# d150_z570m_rev_b.net
KiCad netlist of a schematic drawn in EAGLE
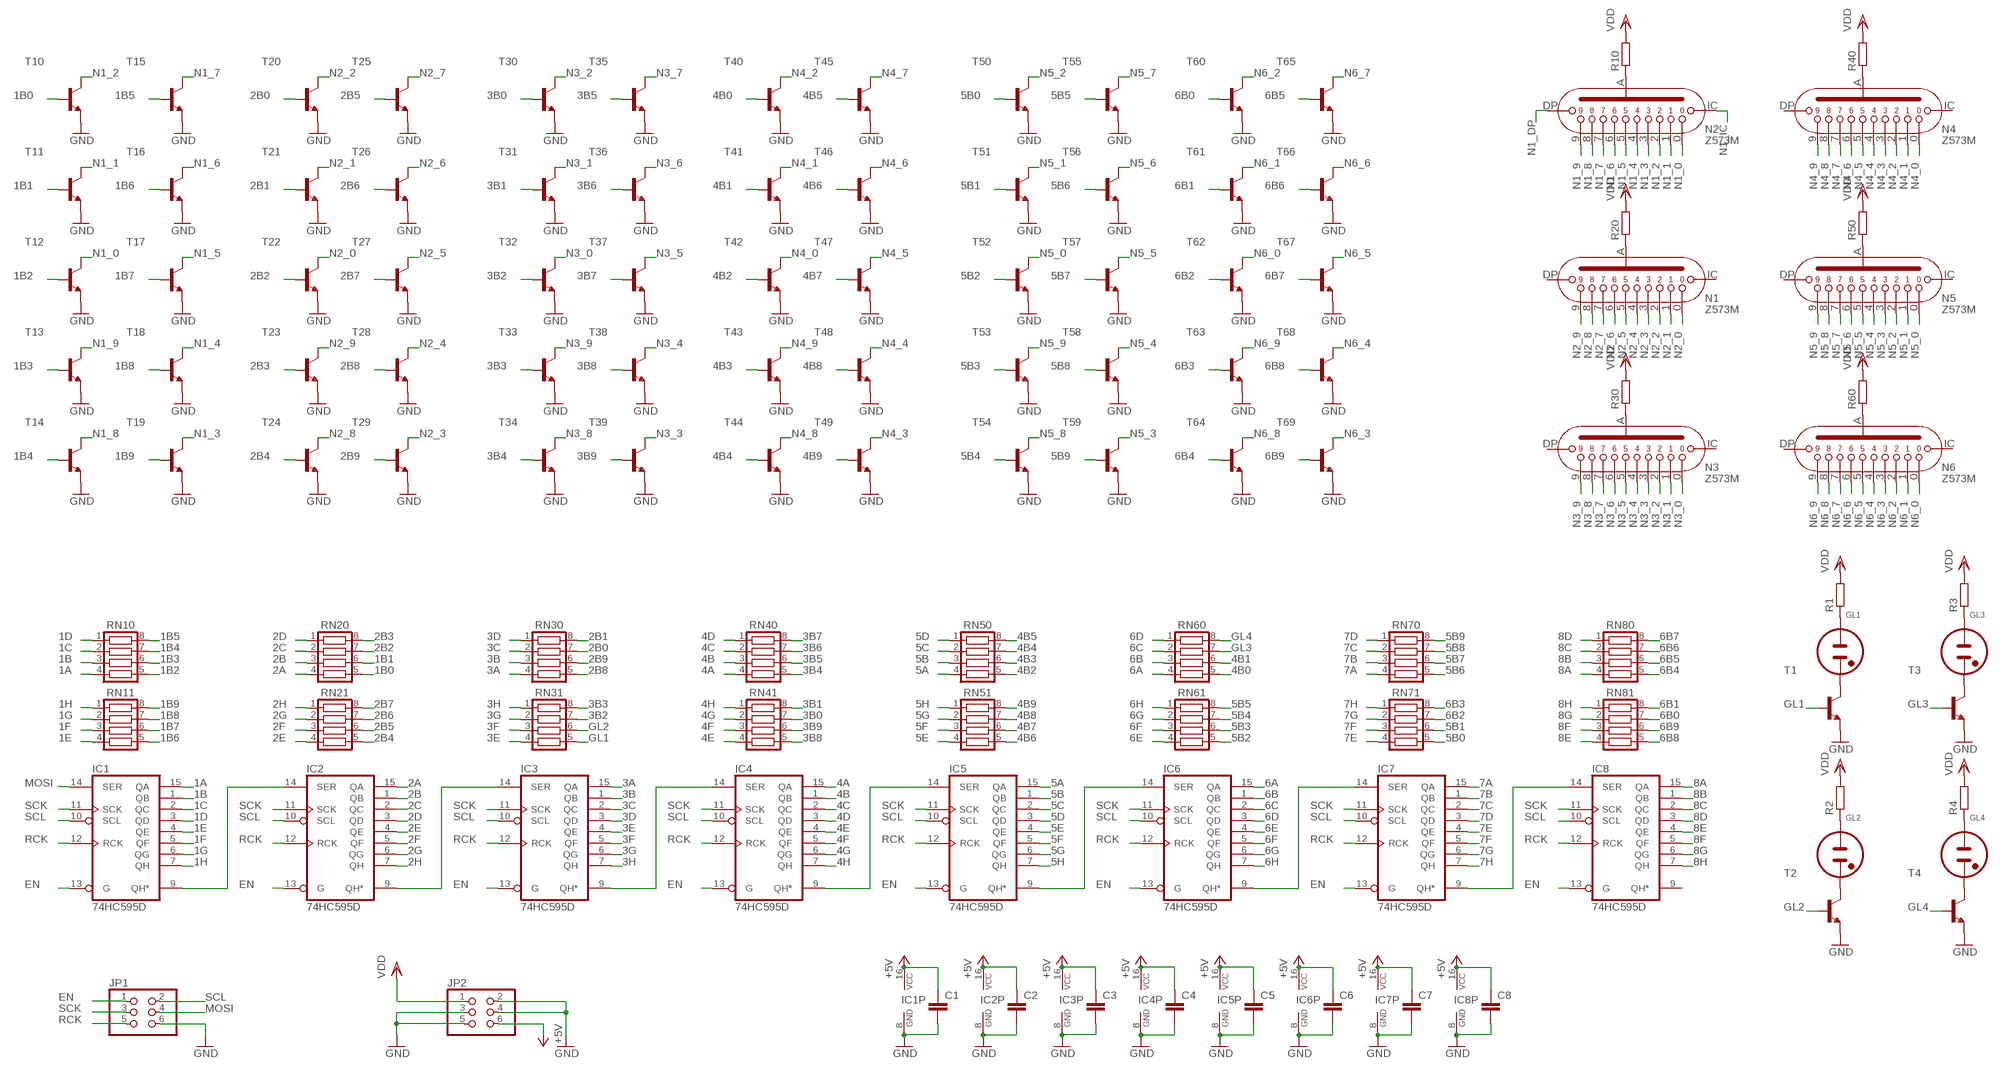
[diagram p0: schematic, sheet 1]

(export (version "E")
  (design (tool "Eeschema 10.0.6"))
  (components
    (comp (ref "C1")
      (value "C-EUC0603")
      (footprint "eagle-import:C0603")
      (libsource (lib "eagle-import") (part "C-EUC0603"))
    )
    (comp (ref "C2")
      (value "C-EUC0603")
      (footprint "eagle-import:C0603")
      (libsource (lib "eagle-import") (part "C-EUC0603"))
    )
    (comp (ref "C3")
      (value "C-EUC0603")
      (footprint "eagle-import:C0603")
      (libsource (lib "eagle-import") (part "C-EUC0603"))
    )
    (comp (ref "C4")
      (value "C-EUC0603")
      (footprint "eagle-import:C0603")
      (libsource (lib "eagle-import") (part "C-EUC0603"))
    )
    (comp (ref "C5")
      (value "C-EUC0603")
      (footprint "eagle-import:C0603")
      (libsource (lib "eagle-import") (part "C-EUC0603"))
    )
    (comp (ref "C6")
      (value "C-EUC0603")
      (footprint "eagle-import:C0603")
      (libsource (lib "eagle-import") (part "C-EUC0603"))
    )
    (comp (ref "C7")
      (value "C-EUC0603")
      (footprint "eagle-import:C0603")
      (libsource (lib "eagle-import") (part "C-EUC0603"))
    )
    (comp (ref "C8")
      (value "C-EUC0603")
      (footprint "eagle-import:C0603")
      (libsource (lib "eagle-import") (part "C-EUC0603"))
    )
    (comp (ref "GL1")
      (value "NE2-NEON-BULB-DRILL")
      (footprint "eagle-import:NE2-NEON-BULB-DRILL")
      (libsource (lib "eagle-import") (part "NE2-NEON-BULB-DRILL"))
    )
    (comp (ref "GL2")
      (value "NE2-NEON-BULB-DRILL")
      (footprint "eagle-import:NE2-NEON-BULB-DRILL")
      (libsource (lib "eagle-import") (part "NE2-NEON-BULB-DRILL"))
    )
    (comp (ref "GL3")
      (value "NE2-NEON-BULB-DRILL")
      (footprint "eagle-import:NE2-NEON-BULB-DRILL")
      (libsource (lib "eagle-import") (part "NE2-NEON-BULB-DRILL"))
    )
    (comp (ref "GL4")
      (value "NE2-NEON-BULB-DRILL")
      (footprint "eagle-import:NE2-NEON-BULB-DRILL")
      (libsource (lib "eagle-import") (part "NE2-NEON-BULB-DRILL"))
    )
    (comp (ref "IC1")
      (value "74HC595D")
      (footprint "eagle-import:SO16")
      (libsource (lib "eagle-import") (part "74595DHC"))
    )
    (comp (ref "IC2")
      (value "74HC595D")
      (footprint "eagle-import:SO16")
      (libsource (lib "eagle-import") (part "74595DHC"))
    )
    (comp (ref "IC3")
      (value "74HC595D")
      (footprint "eagle-import:SO16")
      (libsource (lib "eagle-import") (part "74595DHC"))
    )
    (comp (ref "IC4")
      (value "74HC595D")
      (footprint "eagle-import:SO16")
      (libsource (lib "eagle-import") (part "74595DHC"))
    )
    (comp (ref "IC5")
      (value "74HC595D")
      (footprint "eagle-import:SO16")
      (libsource (lib "eagle-import") (part "74595DHC"))
    )
    (comp (ref "IC6")
      (value "74HC595D")
      (footprint "eagle-import:SO16")
      (libsource (lib "eagle-import") (part "74595DHC"))
    )
    (comp (ref "IC7")
      (value "74HC595D")
      (footprint "eagle-import:SO16")
      (libsource (lib "eagle-import") (part "74595DHC"))
    )
    (comp (ref "IC8")
      (value "74HC595D")
      (footprint "eagle-import:SO16")
      (libsource (lib "eagle-import") (part "74595DHC"))
    )
    (comp (ref "JP1")
      (value "PINHD-2X3_2.54-SMD")
      (footprint "eagle-import:2X03SMD")
      (libsource (lib "eagle-import") (part "PINHD-2X3_2.54-SMD"))
    )
    (comp (ref "JP2")
      (value "PINHD-2X3_2.54-SMD")
      (footprint "eagle-import:2X03SMD")
      (libsource (lib "eagle-import") (part "PINHD-2X3_2.54-SMD"))
    )
    (comp (ref "N1")
      (value "Z573M")
      (footprint "eagle-import:Z57XX")
      (libsource (lib "eagle-import") (part "Z573M"))
    )
    (comp (ref "N2")
      (value "Z573M")
      (footprint "eagle-import:Z57XX")
      (libsource (lib "eagle-import") (part "Z573M"))
    )
    (comp (ref "N3")
      (value "Z573M")
      (footprint "eagle-import:Z57XX")
      (libsource (lib "eagle-import") (part "Z573M"))
    )
    (comp (ref "N4")
      (value "Z573M")
      (footprint "eagle-import:Z57XX")
      (libsource (lib "eagle-import") (part "Z573M"))
    )
    (comp (ref "N5")
      (value "Z573M")
      (footprint "eagle-import:Z57XX")
      (libsource (lib "eagle-import") (part "Z573M"))
    )
    (comp (ref "N6")
      (value "Z573M")
      (footprint "eagle-import:Z57XX")
      (libsource (lib "eagle-import") (part "Z573M"))
    )
    (comp (ref "R1")
      (value "R-EU_R0603")
      (footprint "eagle-import:R0603")
      (libsource (lib "eagle-import") (part "R-EU_R0603"))
    )
    (comp (ref "R2")
      (value "R-EU_R0603")
      (footprint "eagle-import:R0603")
      (libsource (lib "eagle-import") (part "R-EU_R0603"))
    )
    (comp (ref "R3")
      (value "R-EU_R0603")
      (footprint "eagle-import:R0603")
      (libsource (lib "eagle-import") (part "R-EU_R0603"))
    )
    (comp (ref "R4")
      (value "R-EU_R0603")
      (footprint "eagle-import:R0603")
      (libsource (lib "eagle-import") (part "R-EU_R0603"))
    )
    (comp (ref "R10")
      (value "R-EU_R0603")
      (footprint "eagle-import:R0603")
      (libsource (lib "eagle-import") (part "R-EU_R0603"))
    )
    (comp (ref "R20")
      (value "R-EU_R0603")
      (footprint "eagle-import:R0603")
      (libsource (lib "eagle-import") (part "R-EU_R0603"))
    )
    (comp (ref "R30")
      (value "R-EU_R0603")
      (footprint "eagle-import:R0603")
      (libsource (lib "eagle-import") (part "R-EU_R0603"))
    )
    (comp (ref "R40")
      (value "R-EU_R0603")
      (footprint "eagle-import:R0603")
      (libsource (lib "eagle-import") (part "R-EU_R0603"))
    )
    (comp (ref "R50")
      (value "R-EU_R0603")
      (footprint "eagle-import:R0603")
      (libsource (lib "eagle-import") (part "R-EU_R0603"))
    )
    (comp (ref "R60")
      (value "R-EU_R0603")
      (footprint "eagle-import:R0603")
      (libsource (lib "eagle-import") (part "R-EU_R0603"))
    )
    (comp (ref "RN10")
      (value "CTS742C083")
      (footprint "eagle-import:CTS742C083")
      (fields (field (name "OC_FARNELL") "unknown") (field (name "OC_NEWARK") "unknown"))
      (libsource (lib "eagle-import") (part "CTS742C083"))
    )
    (comp (ref "RN11")
      (value "CTS742C083")
      (footprint "eagle-import:CTS742C083")
      (fields (field (name "OC_FARNELL") "unknown") (field (name "OC_NEWARK") "unknown"))
      (libsource (lib "eagle-import") (part "CTS742C083"))
    )
    (comp (ref "RN20")
      (value "CTS742C083")
      (footprint "eagle-import:CTS742C083")
      (fields (field (name "OC_FARNELL") "unknown") (field (name "OC_NEWARK") "unknown"))
      (libsource (lib "eagle-import") (part "CTS742C083"))
    )
    (comp (ref "RN21")
      (value "CTS742C083")
      (footprint "eagle-import:CTS742C083")
      (fields (field (name "OC_FARNELL") "unknown") (field (name "OC_NEWARK") "unknown"))
      (libsource (lib "eagle-import") (part "CTS742C083"))
    )
    (comp (ref "RN30")
      (value "CTS742C083")
      (footprint "eagle-import:CTS742C083")
      (fields (field (name "OC_FARNELL") "unknown") (field (name "OC_NEWARK") "unknown"))
      (libsource (lib "eagle-import") (part "CTS742C083"))
    )
    (comp (ref "RN31")
      (value "CTS742C083")
      (footprint "eagle-import:CTS742C083")
      (fields (field (name "OC_FARNELL") "unknown") (field (name "OC_NEWARK") "unknown"))
      (libsource (lib "eagle-import") (part "CTS742C083"))
    )
    (comp (ref "RN40")
      (value "CTS742C083")
      (footprint "eagle-import:CTS742C083")
      (fields (field (name "OC_FARNELL") "unknown") (field (name "OC_NEWARK") "unknown"))
      (libsource (lib "eagle-import") (part "CTS742C083"))
    )
    (comp (ref "RN41")
      (value "CTS742C083")
      (footprint "eagle-import:CTS742C083")
      (fields (field (name "OC_FARNELL") "unknown") (field (name "OC_NEWARK") "unknown"))
      (libsource (lib "eagle-import") (part "CTS742C083"))
    )
    (comp (ref "RN50")
      (value "CTS742C083")
      (footprint "eagle-import:CTS742C083")
      (fields (field (name "OC_FARNELL") "unknown") (field (name "OC_NEWARK") "unknown"))
      (libsource (lib "eagle-import") (part "CTS742C083"))
    )
    (comp (ref "RN51")
      (value "CTS742C083")
      (footprint "eagle-import:CTS742C083")
      (fields (field (name "OC_FARNELL") "unknown") (field (name "OC_NEWARK") "unknown"))
      (libsource (lib "eagle-import") (part "CTS742C083"))
    )
    (comp (ref "RN60")
      (value "CTS742C083")
      (footprint "eagle-import:CTS742C083")
      (fields (field (name "OC_FARNELL") "unknown") (field (name "OC_NEWARK") "unknown"))
      (libsource (lib "eagle-import") (part "CTS742C083"))
    )
    (comp (ref "RN61")
      (value "CTS742C083")
      (footprint "eagle-import:CTS742C083")
      (fields (field (name "OC_FARNELL") "unknown") (field (name "OC_NEWARK") "unknown"))
      (libsource (lib "eagle-import") (part "CTS742C083"))
    )
    (comp (ref "RN70")
      (value "CTS742C083")
      (footprint "eagle-import:CTS742C083")
      (fields (field (name "OC_FARNELL") "unknown") (field (name "OC_NEWARK") "unknown"))
      (libsource (lib "eagle-import") (part "CTS742C083"))
    )
    (comp (ref "RN71")
      (value "CTS742C083")
      (footprint "eagle-import:CTS742C083")
      (fields (field (name "OC_FARNELL") "unknown") (field (name "OC_NEWARK") "unknown"))
      (libsource (lib "eagle-import") (part "CTS742C083"))
    )
    (comp (ref "RN80")
      (value "CTS742C083")
      (footprint "eagle-import:CTS742C083")
      (fields (field (name "OC_FARNELL") "unknown") (field (name "OC_NEWARK") "unknown"))
      (libsource (lib "eagle-import") (part "CTS742C083"))
    )
    (comp (ref "RN81")
      (value "CTS742C083")
      (footprint "eagle-import:CTS742C083")
      (fields (field (name "OC_FARNELL") "unknown") (field (name "OC_NEWARK") "unknown"))
      (libsource (lib "eagle-import") (part "CTS742C083"))
    )
    (comp (ref "T1")
      (value "SMBTA42")
      (footprint "eagle-import:SOT23")
      (libsource (lib "eagle-import") (part "SMBTA42"))
    )
    (comp (ref "T2")
      (value "SMBTA42")
      (footprint "eagle-import:SOT23")
      (libsource (lib "eagle-import") (part "SMBTA42"))
    )
    (comp (ref "T3")
      (value "SMBTA42")
      (footprint "eagle-import:SOT23")
      (libsource (lib "eagle-import") (part "SMBTA42"))
    )
    (comp (ref "T4")
      (value "SMBTA42")
      (footprint "eagle-import:SOT23")
      (libsource (lib "eagle-import") (part "SMBTA42"))
    )
    (comp (ref "T10")
      (value "SMBTA42")
      (footprint "eagle-import:SOT23")
      (libsource (lib "eagle-import") (part "SMBTA42"))
    )
    (comp (ref "T11")
      (value "SMBTA42")
      (footprint "eagle-import:SOT23")
      (libsource (lib "eagle-import") (part "SMBTA42"))
    )
    (comp (ref "T12")
      (value "SMBTA42")
      (footprint "eagle-import:SOT23")
      (libsource (lib "eagle-import") (part "SMBTA42"))
    )
    (comp (ref "T13")
      (value "SMBTA42")
      (footprint "eagle-import:SOT23")
      (libsource (lib "eagle-import") (part "SMBTA42"))
    )
    (comp (ref "T14")
      (value "SMBTA42")
      (footprint "eagle-import:SOT23")
      (libsource (lib "eagle-import") (part "SMBTA42"))
    )
    (comp (ref "T15")
      (value "SMBTA42")
      (footprint "eagle-import:SOT23")
      (libsource (lib "eagle-import") (part "SMBTA42"))
    )
    (comp (ref "T16")
      (value "SMBTA42")
      (footprint "eagle-import:SOT23")
      (libsource (lib "eagle-import") (part "SMBTA42"))
    )
    (comp (ref "T17")
      (value "SMBTA42")
      (footprint "eagle-import:SOT23")
      (libsource (lib "eagle-import") (part "SMBTA42"))
    )
    (comp (ref "T18")
      (value "SMBTA42")
      (footprint "eagle-import:SOT23")
      (libsource (lib "eagle-import") (part "SMBTA42"))
    )
    (comp (ref "T19")
      (value "SMBTA42")
      (footprint "eagle-import:SOT23")
      (libsource (lib "eagle-import") (part "SMBTA42"))
    )
    (comp (ref "T20")
      (value "SMBTA42")
      (footprint "eagle-import:SOT23")
      (libsource (lib "eagle-import") (part "SMBTA42"))
    )
    (comp (ref "T21")
      (value "SMBTA42")
      (footprint "eagle-import:SOT23")
      (libsource (lib "eagle-import") (part "SMBTA42"))
    )
    (comp (ref "T22")
      (value "SMBTA42")
      (footprint "eagle-import:SOT23")
      (libsource (lib "eagle-import") (part "SMBTA42"))
    )
    (comp (ref "T23")
      (value "SMBTA42")
      (footprint "eagle-import:SOT23")
      (libsource (lib "eagle-import") (part "SMBTA42"))
    )
    (comp (ref "T24")
      (value "SMBTA42")
      (footprint "eagle-import:SOT23")
      (libsource (lib "eagle-import") (part "SMBTA42"))
    )
    (comp (ref "T25")
      (value "SMBTA42")
      (footprint "eagle-import:SOT23")
      (libsource (lib "eagle-import") (part "SMBTA42"))
    )
    (comp (ref "T26")
      (value "SMBTA42")
      (footprint "eagle-import:SOT23")
      (libsource (lib "eagle-import") (part "SMBTA42"))
    )
    (comp (ref "T27")
      (value "SMBTA42")
      (footprint "eagle-import:SOT23")
      (libsource (lib "eagle-import") (part "SMBTA42"))
    )
    (comp (ref "T28")
      (value "SMBTA42")
      (footprint "eagle-import:SOT23")
      (libsource (lib "eagle-import") (part "SMBTA42"))
    )
    (comp (ref "T29")
      (value "SMBTA42")
      (footprint "eagle-import:SOT23")
      (libsource (lib "eagle-import") (part "SMBTA42"))
    )
    (comp (ref "T30")
      (value "SMBTA42")
      (footprint "eagle-import:SOT23")
      (libsource (lib "eagle-import") (part "SMBTA42"))
    )
    (comp (ref "T31")
      (value "SMBTA42")
      (footprint "eagle-import:SOT23")
      (libsource (lib "eagle-import") (part "SMBTA42"))
    )
    (comp (ref "T32")
      (value "SMBTA42")
      (footprint "eagle-import:SOT23")
      (libsource (lib "eagle-import") (part "SMBTA42"))
    )
    (comp (ref "T33")
      (value "SMBTA42")
      (footprint "eagle-import:SOT23")
      (libsource (lib "eagle-import") (part "SMBTA42"))
    )
    (comp (ref "T34")
      (value "SMBTA42")
      (footprint "eagle-import:SOT23")
      (libsource (lib "eagle-import") (part "SMBTA42"))
    )
    (comp (ref "T35")
      (value "SMBTA42")
      (footprint "eagle-import:SOT23")
      (libsource (lib "eagle-import") (part "SMBTA42"))
    )
    (comp (ref "T36")
      (value "SMBTA42")
      (footprint "eagle-import:SOT23")
      (libsource (lib "eagle-import") (part "SMBTA42"))
    )
    (comp (ref "T37")
      (value "SMBTA42")
      (footprint "eagle-import:SOT23")
      (libsource (lib "eagle-import") (part "SMBTA42"))
    )
    (comp (ref "T38")
      (value "SMBTA42")
      (footprint "eagle-import:SOT23")
      (libsource (lib "eagle-import") (part "SMBTA42"))
    )
    (comp (ref "T39")
      (value "SMBTA42")
      (footprint "eagle-import:SOT23")
      (libsource (lib "eagle-import") (part "SMBTA42"))
    )
    (comp (ref "T40")
      (value "SMBTA42")
      (footprint "eagle-import:SOT23")
      (libsource (lib "eagle-import") (part "SMBTA42"))
    )
    (comp (ref "T41")
      (value "SMBTA42")
      (footprint "eagle-import:SOT23")
      (libsource (lib "eagle-import") (part "SMBTA42"))
    )
    (comp (ref "T42")
      (value "SMBTA42")
      (footprint "eagle-import:SOT23")
      (libsource (lib "eagle-import") (part "SMBTA42"))
    )
    (comp (ref "T43")
      (value "SMBTA42")
      (footprint "eagle-import:SOT23")
      (libsource (lib "eagle-import") (part "SMBTA42"))
    )
    (comp (ref "T44")
      (value "SMBTA42")
      (footprint "eagle-import:SOT23")
      (libsource (lib "eagle-import") (part "SMBTA42"))
    )
    (comp (ref "T45")
      (value "SMBTA42")
      (footprint "eagle-import:SOT23")
      (libsource (lib "eagle-import") (part "SMBTA42"))
    )
    (comp (ref "T46")
      (value "SMBTA42")
      (footprint "eagle-import:SOT23")
      (libsource (lib "eagle-import") (part "SMBTA42"))
    )
    (comp (ref "T47")
      (value "SMBTA42")
      (footprint "eagle-import:SOT23")
      (libsource (lib "eagle-import") (part "SMBTA42"))
    )
    (comp (ref "T48")
      (value "SMBTA42")
      (footprint "eagle-import:SOT23")
      (libsource (lib "eagle-import") (part "SMBTA42"))
    )
    (comp (ref "T49")
      (value "SMBTA42")
      (footprint "eagle-import:SOT23")
      (libsource (lib "eagle-import") (part "SMBTA42"))
    )
    (comp (ref "T50")
      (value "SMBTA42")
      (footprint "eagle-import:SOT23")
      (libsource (lib "eagle-import") (part "SMBTA42"))
    )
    (comp (ref "T51")
      (value "SMBTA42")
      (footprint "eagle-import:SOT23")
      (libsource (lib "eagle-import") (part "SMBTA42"))
    )
    (comp (ref "T52")
      (value "SMBTA42")
      (footprint "eagle-import:SOT23")
      (libsource (lib "eagle-import") (part "SMBTA42"))
    )
    (comp (ref "T53")
      (value "SMBTA42")
      (footprint "eagle-import:SOT23")
      (libsource (lib "eagle-import") (part "SMBTA42"))
    )
    (comp (ref "T54")
      (value "SMBTA42")
      (footprint "eagle-import:SOT23")
      (libsource (lib "eagle-import") (part "SMBTA42"))
    )
    (comp (ref "T55")
      (value "SMBTA42")
      (footprint "eagle-import:SOT23")
      (libsource (lib "eagle-import") (part "SMBTA42"))
    )
    (comp (ref "T56")
      (value "SMBTA42")
      (footprint "eagle-import:SOT23")
      (libsource (lib "eagle-import") (part "SMBTA42"))
    )
    (comp (ref "T57")
      (value "SMBTA42")
      (footprint "eagle-import:SOT23")
      (libsource (lib "eagle-import") (part "SMBTA42"))
    )
    (comp (ref "T58")
      (value "SMBTA42")
      (footprint "eagle-import:SOT23")
      (libsource (lib "eagle-import") (part "SMBTA42"))
    )
    (comp (ref "T59")
      (value "SMBTA42")
      (footprint "eagle-import:SOT23")
      (libsource (lib "eagle-import") (part "SMBTA42"))
    )
    (comp (ref "T60")
      (value "SMBTA42")
      (footprint "eagle-import:SOT23")
      (libsource (lib "eagle-import") (part "SMBTA42"))
    )
    (comp (ref "T61")
      (value "SMBTA42")
      (footprint "eagle-import:SOT23")
      (libsource (lib "eagle-import") (part "SMBTA42"))
    )
    (comp (ref "T62")
      (value "SMBTA42")
      (footprint "eagle-import:SOT23")
      (libsource (lib "eagle-import") (part "SMBTA42"))
    )
    (comp (ref "T63")
      (value "SMBTA42")
      (footprint "eagle-import:SOT23")
      (libsource (lib "eagle-import") (part "SMBTA42"))
    )
    (comp (ref "T64")
      (value "SMBTA42")
      (footprint "eagle-import:SOT23")
      (libsource (lib "eagle-import") (part "SMBTA42"))
    )
    (comp (ref "T65")
      (value "SMBTA42")
      (footprint "eagle-import:SOT23")
      (libsource (lib "eagle-import") (part "SMBTA42"))
    )
    (comp (ref "T66")
      (value "SMBTA42")
      (footprint "eagle-import:SOT23")
      (libsource (lib "eagle-import") (part "SMBTA42"))
    )
    (comp (ref "T67")
      (value "SMBTA42")
      (footprint "eagle-import:SOT23")
      (libsource (lib "eagle-import") (part "SMBTA42"))
    )
    (comp (ref "T68")
      (value "SMBTA42")
      (footprint "eagle-import:SOT23")
      (libsource (lib "eagle-import") (part "SMBTA42"))
    )
    (comp (ref "T69")
      (value "SMBTA42")
      (footprint "eagle-import:SOT23")
      (libsource (lib "eagle-import") (part "SMBTA42"))
    )
  )
  (nets
    (net (code "1") (name "+5V") (class "Default")
      (node (ref "C1") (pin "1") (pinfunction "1_1") (pintype "passive"))
      (node (ref "C2") (pin "1") (pinfunction "1_1") (pintype "passive"))
      (node (ref "C3") (pin "1") (pinfunction "1_1") (pintype "passive"))
      (node (ref "C4") (pin "1") (pinfunction "1_1") (pintype "passive"))
      (node (ref "C5") (pin "1") (pinfunction "1_1") (pintype "passive"))
      (node (ref "C6") (pin "1") (pinfunction "1_1") (pintype "passive"))
      (node (ref "C7") (pin "1") (pinfunction "1_1") (pintype "passive"))
      (node (ref "C8") (pin "1") (pinfunction "1_1") (pintype "passive"))
      (node (ref "IC1") (pin "16") (pinfunction "VCC_16") (pintype "power_in"))
      (node (ref "IC2") (pin "16") (pinfunction "VCC_16") (pintype "power_in"))
      (node (ref "IC3") (pin "16") (pinfunction "VCC_16") (pintype "power_in"))
      (node (ref "IC4") (pin "16") (pinfunction "VCC_16") (pintype "power_in"))
      (node (ref "IC5") (pin "16") (pinfunction "VCC_16") (pintype "power_in"))
      (node (ref "IC6") (pin "16") (pinfunction "VCC_16") (pintype "power_in"))
      (node (ref "IC7") (pin "16") (pinfunction "VCC_16") (pintype "power_in"))
      (node (ref "IC8") (pin "16") (pinfunction "VCC_16") (pintype "power_in"))
      (node (ref "JP2") (pin "6") (pinfunction "6_6") (pintype "passive"))
    )
    (net (code "2") (name "/1A") (class "Default")
      (node (ref "IC1") (pin "15") (pinfunction "QA_15") (pintype "tri_state"))
      (node (ref "RN10") (pin "4") (pinfunction "4_4") (pintype "passive"))
    )
    (net (code "3") (name "/1B") (class "Default")
      (node (ref "IC1") (pin "1") (pinfunction "QB_1") (pintype "tri_state"))
      (node (ref "RN10") (pin "3") (pinfunction "3_3") (pintype "passive"))
    )
    (net (code "4") (name "/1B0") (class "Default")
      (node (ref "RN20") (pin "5") (pinfunction "5_5") (pintype "passive"))
      (node (ref "T10") (pin "1") (pinfunction "B_1") (pintype "passive"))
    )
    (net (code "5") (name "/1B1") (class "Default")
      (node (ref "RN20") (pin "6") (pinfunction "6_6") (pintype "passive"))
      (node (ref "T11") (pin "1") (pinfunction "B_1") (pintype "passive"))
    )
    (net (code "6") (name "/1B2") (class "Default")
      (node (ref "RN10") (pin "5") (pinfunction "5_5") (pintype "passive"))
      (node (ref "T12") (pin "1") (pinfunction "B_1") (pintype "passive"))
    )
    (net (code "7") (name "/1B3") (class "Default")
      (node (ref "RN10") (pin "6") (pinfunction "6_6") (pintype "passive"))
      (node (ref "T13") (pin "1") (pinfunction "B_1") (pintype "passive"))
    )
    (net (code "8") (name "/1B4") (class "Default")
      (node (ref "RN10") (pin "7") (pinfunction "7_7") (pintype "passive"))
      (node (ref "T14") (pin "1") (pinfunction "B_1") (pintype "passive"))
    )
    (net (code "9") (name "/1B5") (class "Default")
      (node (ref "RN10") (pin "8") (pinfunction "8_8") (pintype "passive"))
      (node (ref "T15") (pin "1") (pinfunction "B_1") (pintype "passive"))
    )
    (net (code "10") (name "/1B6") (class "Default")
      (node (ref "RN11") (pin "5") (pinfunction "5_5") (pintype "passive"))
      (node (ref "T16") (pin "1") (pinfunction "B_1") (pintype "passive"))
    )
    (net (code "11") (name "/1B7") (class "Default")
      (node (ref "RN11") (pin "6") (pinfunction "6_6") (pintype "passive"))
      (node (ref "T17") (pin "1") (pinfunction "B_1") (pintype "passive"))
    )
    (net (code "12") (name "/1B8") (class "Default")
      (node (ref "RN11") (pin "7") (pinfunction "7_7") (pintype "passive"))
      (node (ref "T18") (pin "1") (pinfunction "B_1") (pintype "passive"))
    )
    (net (code "13") (name "/1B9") (class "Default")
      (node (ref "RN11") (pin "8") (pinfunction "8_8") (pintype "passive"))
      (node (ref "T19") (pin "1") (pinfunction "B_1") (pintype "passive"))
    )
    (net (code "14") (name "/1C") (class "Default")
      (node (ref "IC1") (pin "2") (pinfunction "QC_2") (pintype "tri_state"))
      (node (ref "RN10") (pin "2") (pinfunction "2_2") (pintype "passive"))
    )
    (net (code "15") (name "/1D") (class "Default")
      (node (ref "IC1") (pin "3") (pinfunction "QD_3") (pintype "tri_state"))
      (node (ref "RN10") (pin "1") (pinfunction "1_1") (pintype "passive"))
    )
    (net (code "16") (name "/1E") (class "Default")
      (node (ref "IC1") (pin "4") (pinfunction "QE_4") (pintype "tri_state"))
      (node (ref "RN11") (pin "4") (pinfunction "4_4") (pintype "passive"))
    )
    (net (code "17") (name "/1F") (class "Default")
      (node (ref "IC1") (pin "5") (pinfunction "QF_5") (pintype "tri_state"))
      (node (ref "RN11") (pin "3") (pinfunction "3_3") (pintype "passive"))
    )
    (net (code "18") (name "/1G") (class "Default")
      (node (ref "IC1") (pin "6") (pinfunction "QG_6") (pintype "tri_state"))
      (node (ref "RN11") (pin "2") (pinfunction "2_2") (pintype "passive"))
    )
    (net (code "19") (name "/1H") (class "Default")
      (node (ref "IC1") (pin "7") (pinfunction "QH_7") (pintype "tri_state"))
      (node (ref "RN11") (pin "1") (pinfunction "1_1") (pintype "passive"))
    )
    (net (code "20") (name "/2A") (class "Default")
      (node (ref "IC2") (pin "15") (pinfunction "QA_15") (pintype "tri_state"))
      (node (ref "RN20") (pin "4") (pinfunction "4_4") (pintype "passive"))
    )
    (net (code "21") (name "/2B") (class "Default")
      (node (ref "IC2") (pin "1") (pinfunction "QB_1") (pintype "tri_state"))
      (node (ref "RN20") (pin "3") (pinfunction "3_3") (pintype "passive"))
    )
    (net (code "22") (name "/2B0") (class "Default")
      (node (ref "RN30") (pin "7") (pinfunction "7_7") (pintype "passive"))
      (node (ref "T20") (pin "1") (pinfunction "B_1") (pintype "passive"))
    )
    (net (code "23") (name "/2B1") (class "Default")
      (node (ref "RN30") (pin "8") (pinfunction "8_8") (pintype "passive"))
      (node (ref "T21") (pin "1") (pinfunction "B_1") (pintype "passive"))
    )
    (net (code "24") (name "/2B2") (class "Default")
      (node (ref "RN20") (pin "7") (pinfunction "7_7") (pintype "passive"))
      (node (ref "T22") (pin "1") (pinfunction "B_1") (pintype "passive"))
    )
    (net (code "25") (name "/2B3") (class "Default")
      (node (ref "RN20") (pin "8") (pinfunction "8_8") (pintype "passive"))
      (node (ref "T23") (pin "1") (pinfunction "B_1") (pintype "passive"))
    )
    (net (code "26") (name "/2B4") (class "Default")
      (node (ref "RN21") (pin "5") (pinfunction "5_5") (pintype "passive"))
      (node (ref "T24") (pin "1") (pinfunction "B_1") (pintype "passive"))
    )
    (net (code "27") (name "/2B5") (class "Default")
      (node (ref "RN21") (pin "6") (pinfunction "6_6") (pintype "passive"))
      (node (ref "T25") (pin "1") (pinfunction "B_1") (pintype "passive"))
    )
    (net (code "28") (name "/2B6") (class "Default")
      (node (ref "RN21") (pin "7") (pinfunction "7_7") (pintype "passive"))
      (node (ref "T26") (pin "1") (pinfunction "B_1") (pintype "passive"))
    )
    (net (code "29") (name "/2B7") (class "Default")
      (node (ref "RN21") (pin "8") (pinfunction "8_8") (pintype "passive"))
      (node (ref "T27") (pin "1") (pinfunction "B_1") (pintype "passive"))
    )
    (net (code "30") (name "/2B8") (class "Default")
      (node (ref "RN30") (pin "5") (pinfunction "5_5") (pintype "passive"))
      (node (ref "T28") (pin "1") (pinfunction "B_1") (pintype "passive"))
    )
    (net (code "31") (name "/2B9") (class "Default")
      (node (ref "RN30") (pin "6") (pinfunction "6_6") (pintype "passive"))
      (node (ref "T29") (pin "1") (pinfunction "B_1") (pintype "passive"))
    )
    (net (code "32") (name "/2C") (class "Default")
      (node (ref "IC2") (pin "2") (pinfunction "QC_2") (pintype "tri_state"))
      (node (ref "RN20") (pin "2") (pinfunction "2_2") (pintype "passive"))
    )
    (net (code "33") (name "/2D") (class "Default")
      (node (ref "IC2") (pin "3") (pinfunction "QD_3") (pintype "tri_state"))
      (node (ref "RN20") (pin "1") (pinfunction "1_1") (pintype "passive"))
    )
    (net (code "34") (name "/2E") (class "Default")
      (node (ref "IC2") (pin "4") (pinfunction "QE_4") (pintype "tri_state"))
      (node (ref "RN21") (pin "4") (pinfunction "4_4") (pintype "passive"))
    )
    (net (code "35") (name "/2F") (class "Default")
      (node (ref "IC2") (pin "5") (pinfunction "QF_5") (pintype "tri_state"))
      (node (ref "RN21") (pin "3") (pinfunction "3_3") (pintype "passive"))
    )
    (net (code "36") (name "/2G") (class "Default")
      (node (ref "IC2") (pin "6") (pinfunction "QG_6") (pintype "tri_state"))
      (node (ref "RN21") (pin "2") (pinfunction "2_2") (pintype "passive"))
    )
    (net (code "37") (name "/2H") (class "Default")
      (node (ref "IC2") (pin "7") (pinfunction "QH_7") (pintype "tri_state"))
      (node (ref "RN21") (pin "1") (pinfunction "1_1") (pintype "passive"))
    )
    (net (code "38") (name "/3A") (class "Default")
      (node (ref "IC3") (pin "15") (pinfunction "QA_15") (pintype "tri_state"))
      (node (ref "RN30") (pin "4") (pinfunction "4_4") (pintype "passive"))
    )
    (net (code "39") (name "/3B") (class "Default")
      (node (ref "IC3") (pin "1") (pinfunction "QB_1") (pintype "tri_state"))
      (node (ref "RN30") (pin "3") (pinfunction "3_3") (pintype "passive"))
    )
    (net (code "40") (name "/3B0") (class "Default")
      (node (ref "RN41") (pin "7") (pinfunction "7_7") (pintype "passive"))
      (node (ref "T30") (pin "1") (pinfunction "B_1") (pintype "passive"))
    )
    (net (code "41") (name "/3B1") (class "Default")
      (node (ref "RN41") (pin "8") (pinfunction "8_8") (pintype "passive"))
      (node (ref "T31") (pin "1") (pinfunction "B_1") (pintype "passive"))
    )
    (net (code "42") (name "/3B2") (class "Default")
      (node (ref "RN31") (pin "7") (pinfunction "7_7") (pintype "passive"))
      (node (ref "T32") (pin "1") (pinfunction "B_1") (pintype "passive"))
    )
    (net (code "43") (name "/3B3") (class "Default")
      (node (ref "RN31") (pin "8") (pinfunction "8_8") (pintype "passive"))
      (node (ref "T33") (pin "1") (pinfunction "B_1") (pintype "passive"))
    )
    (net (code "44") (name "/3B4") (class "Default")
      (node (ref "RN40") (pin "5") (pinfunction "5_5") (pintype "passive"))
      (node (ref "T34") (pin "1") (pinfunction "B_1") (pintype "passive"))
    )
    (net (code "45") (name "/3B5") (class "Default")
      (node (ref "RN40") (pin "6") (pinfunction "6_6") (pintype "passive"))
      (node (ref "T35") (pin "1") (pinfunction "B_1") (pintype "passive"))
    )
    (net (code "46") (name "/3B6") (class "Default")
      (node (ref "RN40") (pin "7") (pinfunction "7_7") (pintype "passive"))
      (node (ref "T36") (pin "1") (pinfunction "B_1") (pintype "passive"))
    )
    (net (code "47") (name "/3B7") (class "Default")
      (node (ref "RN40") (pin "8") (pinfunction "8_8") (pintype "passive"))
      (node (ref "T37") (pin "1") (pinfunction "B_1") (pintype "passive"))
    )
    (net (code "48") (name "/3B8") (class "Default")
      (node (ref "RN41") (pin "5") (pinfunction "5_5") (pintype "passive"))
      (node (ref "T38") (pin "1") (pinfunction "B_1") (pintype "passive"))
    )
    (net (code "49") (name "/3B9") (class "Default")
      (node (ref "RN41") (pin "6") (pinfunction "6_6") (pintype "passive"))
      (node (ref "T39") (pin "1") (pinfunction "B_1") (pintype "passive"))
    )
    (net (code "50") (name "/3C") (class "Default")
      (node (ref "IC3") (pin "2") (pinfunction "QC_2") (pintype "tri_state"))
      (node (ref "RN30") (pin "2") (pinfunction "2_2") (pintype "passive"))
    )
    (net (code "51") (name "/3D") (class "Default")
      (node (ref "IC3") (pin "3") (pinfunction "QD_3") (pintype "tri_state"))
      (node (ref "RN30") (pin "1") (pinfunction "1_1") (pintype "passive"))
    )
    (net (code "52") (name "/3E") (class "Default")
      (node (ref "IC3") (pin "4") (pinfunction "QE_4") (pintype "tri_state"))
      (node (ref "RN31") (pin "4") (pinfunction "4_4") (pintype "passive"))
    )
    (net (code "53") (name "/3F") (class "Default")
      (node (ref "IC3") (pin "5") (pinfunction "QF_5") (pintype "tri_state"))
      (node (ref "RN31") (pin "3") (pinfunction "3_3") (pintype "passive"))
    )
    (net (code "54") (name "/3G") (class "Default")
      (node (ref "IC3") (pin "6") (pinfunction "QG_6") (pintype "tri_state"))
      (node (ref "RN31") (pin "2") (pinfunction "2_2") (pintype "passive"))
    )
    (net (code "55") (name "/3H") (class "Default")
      (node (ref "IC3") (pin "7") (pinfunction "QH_7") (pintype "tri_state"))
      (node (ref "RN31") (pin "1") (pinfunction "1_1") (pintype "passive"))
    )
    (net (code "56") (name "/4A") (class "Default")
      (node (ref "IC4") (pin "15") (pinfunction "QA_15") (pintype "tri_state"))
      (node (ref "RN40") (pin "4") (pinfunction "4_4") (pintype "passive"))
    )
    (net (code "57") (name "/4B") (class "Default")
      (node (ref "IC4") (pin "1") (pinfunction "QB_1") (pintype "tri_state"))
      (node (ref "RN40") (pin "3") (pinfunction "3_3") (pintype "passive"))
    )
    (net (code "58") (name "/4B0") (class "Default")
      (node (ref "RN60") (pin "5") (pinfunction "5_5") (pintype "passive"))
      (node (ref "T40") (pin "1") (pinfunction "B_1") (pintype "passive"))
    )
    (net (code "59") (name "/4B1") (class "Default")
      (node (ref "RN60") (pin "6") (pinfunction "6_6") (pintype "passive"))
      (node (ref "T41") (pin "1") (pinfunction "B_1") (pintype "passive"))
    )
    (net (code "60") (name "/4B2") (class "Default")
      (node (ref "RN50") (pin "5") (pinfunction "5_5") (pintype "passive"))
      (node (ref "T42") (pin "1") (pinfunction "B_1") (pintype "passive"))
    )
    (net (code "61") (name "/4B3") (class "Default")
      (node (ref "RN50") (pin "6") (pinfunction "6_6") (pintype "passive"))
      (node (ref "T43") (pin "1") (pinfunction "B_1") (pintype "passive"))
    )
    (net (code "62") (name "/4B4") (class "Default")
      (node (ref "RN50") (pin "7") (pinfunction "7_7") (pintype "passive"))
      (node (ref "T44") (pin "1") (pinfunction "B_1") (pintype "passive"))
    )
    (net (code "63") (name "/4B5") (class "Default")
      (node (ref "RN50") (pin "8") (pinfunction "8_8") (pintype "passive"))
      (node (ref "T45") (pin "1") (pinfunction "B_1") (pintype "passive"))
    )
    (net (code "64") (name "/4B6") (class "Default")
      (node (ref "RN51") (pin "5") (pinfunction "5_5") (pintype "passive"))
      (node (ref "T46") (pin "1") (pinfunction "B_1") (pintype "passive"))
    )
    (net (code "65") (name "/4B7") (class "Default")
      (node (ref "RN51") (pin "6") (pinfunction "6_6") (pintype "passive"))
      (node (ref "T47") (pin "1") (pinfunction "B_1") (pintype "passive"))
    )
    (net (code "66") (name "/4B8") (class "Default")
      (node (ref "RN51") (pin "7") (pinfunction "7_7") (pintype "passive"))
      (node (ref "T48") (pin "1") (pinfunction "B_1") (pintype "passive"))
    )
    (net (code "67") (name "/4B9") (class "Default")
      (node (ref "RN51") (pin "8") (pinfunction "8_8") (pintype "passive"))
      (node (ref "T49") (pin "1") (pinfunction "B_1") (pintype "passive"))
    )
    (net (code "68") (name "/4C") (class "Default")
      (node (ref "IC4") (pin "2") (pinfunction "QC_2") (pintype "tri_state"))
      (node (ref "RN40") (pin "2") (pinfunction "2_2") (pintype "passive"))
    )
    (net (code "69") (name "/4D") (class "Default")
      (node (ref "IC4") (pin "3") (pinfunction "QD_3") (pintype "tri_state"))
      (node (ref "RN40") (pin "1") (pinfunction "1_1") (pintype "passive"))
    )
    (net (code "70") (name "/4E") (class "Default")
      (node (ref "IC4") (pin "4") (pinfunction "QE_4") (pintype "tri_state"))
      (node (ref "RN41") (pin "4") (pinfunction "4_4") (pintype "passive"))
    )
    (net (code "71") (name "/4F") (class "Default")
      (node (ref "IC4") (pin "5") (pinfunction "QF_5") (pintype "tri_state"))
      (node (ref "RN41") (pin "3") (pinfunction "3_3") (pintype "passive"))
    )
    (net (code "72") (name "/4G") (class "Default")
      (node (ref "IC4") (pin "6") (pinfunction "QG_6") (pintype "tri_state"))
      (node (ref "RN41") (pin "2") (pinfunction "2_2") (pintype "passive"))
    )
    (net (code "73") (name "/4H") (class "Default")
      (node (ref "IC4") (pin "7") (pinfunction "QH_7") (pintype "tri_state"))
      (node (ref "RN41") (pin "1") (pinfunction "1_1") (pintype "passive"))
    )
    (net (code "74") (name "/5A") (class "Default")
      (node (ref "IC5") (pin "15") (pinfunction "QA_15") (pintype "tri_state"))
      (node (ref "RN50") (pin "4") (pinfunction "4_4") (pintype "passive"))
    )
    (net (code "75") (name "/5B") (class "Default")
      (node (ref "IC5") (pin "1") (pinfunction "QB_1") (pintype "tri_state"))
      (node (ref "RN50") (pin "3") (pinfunction "3_3") (pintype "passive"))
    )
    (net (code "76") (name "/5B0") (class "Default")
      (node (ref "RN71") (pin "5") (pinfunction "5_5") (pintype "passive"))
      (node (ref "T50") (pin "1") (pinfunction "B_1") (pintype "passive"))
    )
    (net (code "77") (name "/5B1") (class "Default")
      (node (ref "RN71") (pin "6") (pinfunction "6_6") (pintype "passive"))
      (node (ref "T51") (pin "1") (pinfunction "B_1") (pintype "passive"))
    )
    (net (code "78") (name "/5B2") (class "Default")
      (node (ref "RN61") (pin "5") (pinfunction "5_5") (pintype "passive"))
      (node (ref "T52") (pin "1") (pinfunction "B_1") (pintype "passive"))
    )
    (net (code "79") (name "/5B3") (class "Default")
      (node (ref "RN61") (pin "6") (pinfunction "6_6") (pintype "passive"))
      (node (ref "T53") (pin "1") (pinfunction "B_1") (pintype "passive"))
    )
    (net (code "80") (name "/5B4") (class "Default")
      (node (ref "RN61") (pin "7") (pinfunction "7_7") (pintype "passive"))
      (node (ref "T54") (pin "1") (pinfunction "B_1") (pintype "passive"))
    )
    (net (code "81") (name "/5B5") (class "Default")
      (node (ref "RN61") (pin "8") (pinfunction "8_8") (pintype "passive"))
      (node (ref "T55") (pin "1") (pinfunction "B_1") (pintype "passive"))
    )
    (net (code "82") (name "/5B6") (class "Default")
      (node (ref "RN70") (pin "5") (pinfunction "5_5") (pintype "passive"))
      (node (ref "T56") (pin "1") (pinfunction "B_1") (pintype "passive"))
    )
    (net (code "83") (name "/5B7") (class "Default")
      (node (ref "RN70") (pin "6") (pinfunction "6_6") (pintype "passive"))
      (node (ref "T57") (pin "1") (pinfunction "B_1") (pintype "passive"))
    )
    (net (code "84") (name "/5B8") (class "Default")
      (node (ref "RN70") (pin "7") (pinfunction "7_7") (pintype "passive"))
      (node (ref "T58") (pin "1") (pinfunction "B_1") (pintype "passive"))
    )
    (net (code "85") (name "/5B9") (class "Default")
      (node (ref "RN70") (pin "8") (pinfunction "8_8") (pintype "passive"))
      (node (ref "T59") (pin "1") (pinfunction "B_1") (pintype "passive"))
    )
    (net (code "86") (name "/5C") (class "Default")
      (node (ref "IC5") (pin "2") (pinfunction "QC_2") (pintype "tri_state"))
      (node (ref "RN50") (pin "2") (pinfunction "2_2") (pintype "passive"))
    )
    (net (code "87") (name "/5D") (class "Default")
      (node (ref "IC5") (pin "3") (pinfunction "QD_3") (pintype "tri_state"))
      (node (ref "RN50") (pin "1") (pinfunction "1_1") (pintype "passive"))
    )
    (net (code "88") (name "/5E") (class "Default")
      (node (ref "IC5") (pin "4") (pinfunction "QE_4") (pintype "tri_state"))
      (node (ref "RN51") (pin "4") (pinfunction "4_4") (pintype "passive"))
    )
    (net (code "89") (name "/5F") (class "Default")
      (node (ref "IC5") (pin "5") (pinfunction "QF_5") (pintype "tri_state"))
      (node (ref "RN51") (pin "3") (pinfunction "3_3") (pintype "passive"))
    )
    (net (code "90") (name "/5G") (class "Default")
      (node (ref "IC5") (pin "6") (pinfunction "QG_6") (pintype "tri_state"))
      (node (ref "RN51") (pin "2") (pinfunction "2_2") (pintype "passive"))
    )
    (net (code "91") (name "/5H") (class "Default")
      (node (ref "IC5") (pin "7") (pinfunction "QH_7") (pintype "tri_state"))
      (node (ref "RN51") (pin "1") (pinfunction "1_1") (pintype "passive"))
    )
    (net (code "92") (name "/6A") (class "Default")
      (node (ref "IC6") (pin "15") (pinfunction "QA_15") (pintype "tri_state"))
      (node (ref "RN60") (pin "4") (pinfunction "4_4") (pintype "passive"))
    )
    (net (code "93") (name "/6B") (class "Default")
      (node (ref "IC6") (pin "1") (pinfunction "QB_1") (pintype "tri_state"))
      (node (ref "RN60") (pin "3") (pinfunction "3_3") (pintype "passive"))
    )
    (net (code "94") (name "/6B0") (class "Default")
      (node (ref "RN81") (pin "7") (pinfunction "7_7") (pintype "passive"))
      (node (ref "T60") (pin "1") (pinfunction "B_1") (pintype "passive"))
    )
    (net (code "95") (name "/6B1") (class "Default")
      (node (ref "RN81") (pin "8") (pinfunction "8_8") (pintype "passive"))
      (node (ref "T61") (pin "1") (pinfunction "B_1") (pintype "passive"))
    )
    (net (code "96") (name "/6B2") (class "Default")
      (node (ref "RN71") (pin "7") (pinfunction "7_7") (pintype "passive"))
      (node (ref "T62") (pin "1") (pinfunction "B_1") (pintype "passive"))
    )
    (net (code "97") (name "/6B3") (class "Default")
      (node (ref "RN71") (pin "8") (pinfunction "8_8") (pintype "passive"))
      (node (ref "T63") (pin "1") (pinfunction "B_1") (pintype "passive"))
    )
    (net (code "98") (name "/6B4") (class "Default")
      (node (ref "RN80") (pin "5") (pinfunction "5_5") (pintype "passive"))
      (node (ref "T64") (pin "1") (pinfunction "B_1") (pintype "passive"))
    )
    (net (code "99") (name "/6B5") (class "Default")
      (node (ref "RN80") (pin "6") (pinfunction "6_6") (pintype "passive"))
      (node (ref "T65") (pin "1") (pinfunction "B_1") (pintype "passive"))
    )
    (net (code "100") (name "/6B6") (class "Default")
      (node (ref "RN80") (pin "7") (pinfunction "7_7") (pintype "passive"))
      (node (ref "T66") (pin "1") (pinfunction "B_1") (pintype "passive"))
    )
    (net (code "101") (name "/6B7") (class "Default")
      (node (ref "RN80") (pin "8") (pinfunction "8_8") (pintype "passive"))
      (node (ref "T67") (pin "1") (pinfunction "B_1") (pintype "passive"))
    )
    (net (code "102") (name "/6B8") (class "Default")
      (node (ref "RN81") (pin "5") (pinfunction "5_5") (pintype "passive"))
      (node (ref "T68") (pin "1") (pinfunction "B_1") (pintype "passive"))
    )
    (net (code "103") (name "/6B9") (class "Default")
      (node (ref "RN81") (pin "6") (pinfunction "6_6") (pintype "passive"))
      (node (ref "T69") (pin "1") (pinfunction "B_1") (pintype "passive"))
    )
    (net (code "104") (name "/6C") (class "Default")
      (node (ref "IC6") (pin "2") (pinfunction "QC_2") (pintype "tri_state"))
      (node (ref "RN60") (pin "2") (pinfunction "2_2") (pintype "passive"))
    )
    (net (code "105") (name "/6D") (class "Default")
      (node (ref "IC6") (pin "3") (pinfunction "QD_3") (pintype "tri_state"))
      (node (ref "RN60") (pin "1") (pinfunction "1_1") (pintype "passive"))
    )
    (net (code "106") (name "/6E") (class "Default")
      (node (ref "IC6") (pin "4") (pinfunction "QE_4") (pintype "tri_state"))
      (node (ref "RN61") (pin "4") (pinfunction "4_4") (pintype "passive"))
    )
    (net (code "107") (name "/6F") (class "Default")
      (node (ref "IC6") (pin "5") (pinfunction "QF_5") (pintype "tri_state"))
      (node (ref "RN61") (pin "3") (pinfunction "3_3") (pintype "passive"))
    )
    (net (code "108") (name "/6G") (class "Default")
      (node (ref "IC6") (pin "6") (pinfunction "QG_6") (pintype "tri_state"))
      (node (ref "RN61") (pin "2") (pinfunction "2_2") (pintype "passive"))
    )
    (net (code "109") (name "/6H") (class "Default")
      (node (ref "IC6") (pin "7") (pinfunction "QH_7") (pintype "tri_state"))
      (node (ref "RN61") (pin "1") (pinfunction "1_1") (pintype "passive"))
    )
    (net (code "110") (name "/7A") (class "Default")
      (node (ref "IC7") (pin "15") (pinfunction "QA_15") (pintype "tri_state"))
      (node (ref "RN70") (pin "4") (pinfunction "4_4") (pintype "passive"))
    )
    (net (code "111") (name "/7B") (class "Default")
      (node (ref "IC7") (pin "1") (pinfunction "QB_1") (pintype "tri_state"))
      (node (ref "RN70") (pin "3") (pinfunction "3_3") (pintype "passive"))
    )
    (net (code "112") (name "/7C") (class "Default")
      (node (ref "IC7") (pin "2") (pinfunction "QC_2") (pintype "tri_state"))
      (node (ref "RN70") (pin "2") (pinfunction "2_2") (pintype "passive"))
    )
    (net (code "113") (name "/7D") (class "Default")
      (node (ref "IC7") (pin "3") (pinfunction "QD_3") (pintype "tri_state"))
      (node (ref "RN70") (pin "1") (pinfunction "1_1") (pintype "passive"))
    )
    (net (code "114") (name "/7E") (class "Default")
      (node (ref "IC7") (pin "4") (pinfunction "QE_4") (pintype "tri_state"))
      (node (ref "RN71") (pin "4") (pinfunction "4_4") (pintype "passive"))
    )
    (net (code "115") (name "/7F") (class "Default")
      (node (ref "IC7") (pin "5") (pinfunction "QF_5") (pintype "tri_state"))
      (node (ref "RN71") (pin "3") (pinfunction "3_3") (pintype "passive"))
    )
    (net (code "116") (name "/7G") (class "Default")
      (node (ref "IC7") (pin "6") (pinfunction "QG_6") (pintype "tri_state"))
      (node (ref "RN71") (pin "2") (pinfunction "2_2") (pintype "passive"))
    )
    (net (code "117") (name "/7H") (class "Default")
      (node (ref "IC7") (pin "7") (pinfunction "QH_7") (pintype "tri_state"))
      (node (ref "RN71") (pin "1") (pinfunction "1_1") (pintype "passive"))
    )
    (net (code "118") (name "/8A") (class "Default")
      (node (ref "IC8") (pin "15") (pinfunction "QA_15") (pintype "tri_state"))
      (node (ref "RN80") (pin "4") (pinfunction "4_4") (pintype "passive"))
    )
    (net (code "119") (name "/8B") (class "Default")
      (node (ref "IC8") (pin "1") (pinfunction "QB_1") (pintype "tri_state"))
      (node (ref "RN80") (pin "3") (pinfunction "3_3") (pintype "passive"))
    )
    (net (code "120") (name "/8C") (class "Default")
      (node (ref "IC8") (pin "2") (pinfunction "QC_2") (pintype "tri_state"))
      (node (ref "RN80") (pin "2") (pinfunction "2_2") (pintype "passive"))
    )
    (net (code "121") (name "/8D") (class "Default")
      (node (ref "IC8") (pin "3") (pinfunction "QD_3") (pintype "tri_state"))
      (node (ref "RN80") (pin "1") (pinfunction "1_1") (pintype "passive"))
    )
    (net (code "122") (name "/8E") (class "Default")
      (node (ref "IC8") (pin "4") (pinfunction "QE_4") (pintype "tri_state"))
      (node (ref "RN81") (pin "4") (pinfunction "4_4") (pintype "passive"))
    )
    (net (code "123") (name "/8F") (class "Default")
      (node (ref "IC8") (pin "5") (pinfunction "QF_5") (pintype "tri_state"))
      (node (ref "RN81") (pin "3") (pinfunction "3_3") (pintype "passive"))
    )
    (net (code "124") (name "/8G") (class "Default")
      (node (ref "IC8") (pin "6") (pinfunction "QG_6") (pintype "tri_state"))
      (node (ref "RN81") (pin "2") (pinfunction "2_2") (pintype "passive"))
    )
    (net (code "125") (name "/8H") (class "Default")
      (node (ref "IC8") (pin "7") (pinfunction "QH_7") (pintype "tri_state"))
      (node (ref "RN81") (pin "1") (pinfunction "1_1") (pintype "passive"))
    )
    (net (code "126") (name "/EN") (class "Default")
      (node (ref "IC1") (pin "13") (pinfunction "G_13") (pintype "input"))
      (node (ref "IC2") (pin "13") (pinfunction "G_13") (pintype "input"))
      (node (ref "IC3") (pin "13") (pinfunction "G_13") (pintype "input"))
      (node (ref "IC4") (pin "13") (pinfunction "G_13") (pintype "input"))
      (node (ref "IC5") (pin "13") (pinfunction "G_13") (pintype "input"))
      (node (ref "IC6") (pin "13") (pinfunction "G_13") (pintype "input"))
      (node (ref "IC7") (pin "13") (pinfunction "G_13") (pintype "input"))
      (node (ref "IC8") (pin "13") (pinfunction "G_13") (pintype "input"))
      (node (ref "JP1") (pin "1") (pinfunction "1_1") (pintype "passive"))
    )
    (net (code "127") (name "/GL1") (class "Default")
      (node (ref "RN31") (pin "5") (pinfunction "5_5") (pintype "passive"))
      (node (ref "T1") (pin "1") (pinfunction "B_1") (pintype "passive"))
    )
    (net (code "128") (name "/GL2") (class "Default")
      (node (ref "RN31") (pin "6") (pinfunction "6_6") (pintype "passive"))
      (node (ref "T2") (pin "1") (pinfunction "B_1") (pintype "passive"))
    )
    (net (code "129") (name "/GL3") (class "Default")
      (node (ref "RN60") (pin "7") (pinfunction "7_7") (pintype "passive"))
      (node (ref "T3") (pin "1") (pinfunction "B_1") (pintype "passive"))
    )
    (net (code "130") (name "/GL4") (class "Default")
      (node (ref "RN60") (pin "8") (pinfunction "8_8") (pintype "passive"))
      (node (ref "T4") (pin "1") (pinfunction "B_1") (pintype "passive"))
    )
    (net (code "131") (name "/MOSI") (class "Default")
      (node (ref "IC1") (pin "14") (pinfunction "SER_14") (pintype "input"))
      (node (ref "JP1") (pin "4") (pinfunction "4_4") (pintype "passive"))
    )
    (net (code "132") (name "/N1_0") (class "Default")
      (node (ref "N2") (pin "12") (pinfunction "0_12") (pintype "bidirectional"))
      (node (ref "T12") (pin "3") (pinfunction "C_3") (pintype "passive"))
    )
    (net (code "133") (name "/N1_1") (class "Default")
      (node (ref "N2") (pin "1") (pinfunction "1_1") (pintype "bidirectional"))
      (node (ref "T11") (pin "3") (pinfunction "C_3") (pintype "passive"))
    )
    (net (code "134") (name "/N1_2") (class "Default")
      (node (ref "N2") (pin "2") (pinfunction "2_2") (pintype "bidirectional"))
      (node (ref "T10") (pin "3") (pinfunction "C_3") (pintype "passive"))
    )
    (net (code "135") (name "/N1_3") (class "Default")
      (node (ref "N2") (pin "3") (pinfunction "3_3") (pintype "bidirectional"))
      (node (ref "T19") (pin "3") (pinfunction "C_3") (pintype "passive"))
    )
    (net (code "136") (name "/N1_4") (class "Default")
      (node (ref "N2") (pin "5") (pinfunction "4_5") (pintype "bidirectional"))
      (node (ref "T18") (pin "3") (pinfunction "C_3") (pintype "passive"))
    )
    (net (code "137") (name "/N1_5") (class "Default")
      (node (ref "N2") (pin "6") (pinfunction "5_6") (pintype "bidirectional"))
      (node (ref "T17") (pin "3") (pinfunction "C_3") (pintype "passive"))
    )
    (net (code "138") (name "/N1_6") (class "Default")
      (node (ref "N2") (pin "7") (pinfunction "6_7") (pintype "bidirectional"))
      (node (ref "T16") (pin "3") (pinfunction "C_3") (pintype "passive"))
    )
    (net (code "139") (name "/N1_7") (class "Default")
      (node (ref "N2") (pin "8") (pinfunction "7_8") (pintype "bidirectional"))
      (node (ref "T15") (pin "3") (pinfunction "C_3") (pintype "passive"))
    )
    (net (code "140") (name "/N1_8") (class "Default")
      (node (ref "N2") (pin "9") (pinfunction "8_9") (pintype "bidirectional"))
      (node (ref "T14") (pin "3") (pinfunction "C_3") (pintype "passive"))
    )
    (net (code "141") (name "/N1_9") (class "Default")
      (node (ref "N2") (pin "11") (pinfunction "9_11") (pintype "bidirectional"))
      (node (ref "T13") (pin "3") (pinfunction "C_3") (pintype "passive"))
    )
    (net (code "142") (name "/N1_DP") (class "Default")
      (node (ref "N2") (pin "10") (pinfunction "DP_10") (pintype "bidirectional"))
    )
    (net (code "143") (name "/N1_IC") (class "Default")
      (node (ref "N2") (pin "4") (pinfunction "IC_4") (pintype "bidirectional"))
    )
    (net (code "144") (name "/N2_0") (class "Default")
      (node (ref "N1") (pin "12") (pinfunction "0_12") (pintype "bidirectional"))
      (node (ref "T22") (pin "3") (pinfunction "C_3") (pintype "passive"))
    )
    (net (code "145") (name "/N2_1") (class "Default")
      (node (ref "N1") (pin "1") (pinfunction "1_1") (pintype "bidirectional"))
      (node (ref "T21") (pin "3") (pinfunction "C_3") (pintype "passive"))
    )
    (net (code "146") (name "/N2_2") (class "Default")
      (node (ref "N1") (pin "2") (pinfunction "2_2") (pintype "bidirectional"))
      (node (ref "T20") (pin "3") (pinfunction "C_3") (pintype "passive"))
    )
    (net (code "147") (name "/N2_3") (class "Default")
      (node (ref "N1") (pin "3") (pinfunction "3_3") (pintype "bidirectional"))
      (node (ref "T29") (pin "3") (pinfunction "C_3") (pintype "passive"))
    )
    (net (code "148") (name "/N2_4") (class "Default")
      (node (ref "N1") (pin "5") (pinfunction "4_5") (pintype "bidirectional"))
      (node (ref "T28") (pin "3") (pinfunction "C_3") (pintype "passive"))
    )
    (net (code "149") (name "/N2_5") (class "Default")
      (node (ref "N1") (pin "6") (pinfunction "5_6") (pintype "bidirectional"))
      (node (ref "T27") (pin "3") (pinfunction "C_3") (pintype "passive"))
    )
    (net (code "150") (name "/N2_6") (class "Default")
      (node (ref "N1") (pin "7") (pinfunction "6_7") (pintype "bidirectional"))
      (node (ref "T26") (pin "3") (pinfunction "C_3") (pintype "passive"))
    )
    (net (code "151") (name "/N2_7") (class "Default")
      (node (ref "N1") (pin "8") (pinfunction "7_8") (pintype "bidirectional"))
      (node (ref "T25") (pin "3") (pinfunction "C_3") (pintype "passive"))
    )
    (net (code "152") (name "/N2_8") (class "Default")
      (node (ref "N1") (pin "9") (pinfunction "8_9") (pintype "bidirectional"))
      (node (ref "T24") (pin "3") (pinfunction "C_3") (pintype "passive"))
    )
    (net (code "153") (name "/N2_9") (class "Default")
      (node (ref "N1") (pin "11") (pinfunction "9_11") (pintype "bidirectional"))
      (node (ref "T23") (pin "3") (pinfunction "C_3") (pintype "passive"))
    )
    (net (code "154") (name "/N3_0") (class "Default")
      (node (ref "N3") (pin "12") (pinfunction "0_12") (pintype "bidirectional"))
      (node (ref "T32") (pin "3") (pinfunction "C_3") (pintype "passive"))
    )
    (net (code "155") (name "/N3_1") (class "Default")
      (node (ref "N3") (pin "1") (pinfunction "1_1") (pintype "bidirectional"))
      (node (ref "T31") (pin "3") (pinfunction "C_3") (pintype "passive"))
    )
    (net (code "156") (name "/N3_2") (class "Default")
      (node (ref "N3") (pin "2") (pinfunction "2_2") (pintype "bidirectional"))
      (node (ref "T30") (pin "3") (pinfunction "C_3") (pintype "passive"))
    )
    (net (code "157") (name "/N3_3") (class "Default")
      (node (ref "N3") (pin "3") (pinfunction "3_3") (pintype "bidirectional"))
      (node (ref "T39") (pin "3") (pinfunction "C_3") (pintype "passive"))
    )
    (net (code "158") (name "/N3_4") (class "Default")
      (node (ref "N3") (pin "5") (pinfunction "4_5") (pintype "bidirectional"))
      (node (ref "T38") (pin "3") (pinfunction "C_3") (pintype "passive"))
    )
    (net (code "159") (name "/N3_5") (class "Default")
      (node (ref "N3") (pin "6") (pinfunction "5_6") (pintype "bidirectional"))
      (node (ref "T37") (pin "3") (pinfunction "C_3") (pintype "passive"))
    )
    (net (code "160") (name "/N3_6") (class "Default")
      (node (ref "N3") (pin "7") (pinfunction "6_7") (pintype "bidirectional"))
      (node (ref "T36") (pin "3") (pinfunction "C_3") (pintype "passive"))
    )
    (net (code "161") (name "/N3_7") (class "Default")
      (node (ref "N3") (pin "8") (pinfunction "7_8") (pintype "bidirectional"))
      (node (ref "T35") (pin "3") (pinfunction "C_3") (pintype "passive"))
    )
    (net (code "162") (name "/N3_8") (class "Default")
      (node (ref "N3") (pin "9") (pinfunction "8_9") (pintype "bidirectional"))
      (node (ref "T34") (pin "3") (pinfunction "C_3") (pintype "passive"))
    )
    (net (code "163") (name "/N3_9") (class "Default")
      (node (ref "N3") (pin "11") (pinfunction "9_11") (pintype "bidirectional"))
      (node (ref "T33") (pin "3") (pinfunction "C_3") (pintype "passive"))
    )
    (net (code "164") (name "/N4_0") (class "Default")
      (node (ref "N4") (pin "12") (pinfunction "0_12") (pintype "bidirectional"))
      (node (ref "T42") (pin "3") (pinfunction "C_3") (pintype "passive"))
    )
    (net (code "165") (name "/N4_1") (class "Default")
      (node (ref "N4") (pin "1") (pinfunction "1_1") (pintype "bidirectional"))
      (node (ref "T41") (pin "3") (pinfunction "C_3") (pintype "passive"))
    )
    (net (code "166") (name "/N4_2") (class "Default")
      (node (ref "N4") (pin "2") (pinfunction "2_2") (pintype "bidirectional"))
      (node (ref "T40") (pin "3") (pinfunction "C_3") (pintype "passive"))
    )
    (net (code "167") (name "/N4_3") (class "Default")
      (node (ref "N4") (pin "3") (pinfunction "3_3") (pintype "bidirectional"))
      (node (ref "T49") (pin "3") (pinfunction "C_3") (pintype "passive"))
    )
    (net (code "168") (name "/N4_4") (class "Default")
      (node (ref "N4") (pin "5") (pinfunction "4_5") (pintype "bidirectional"))
      (node (ref "T48") (pin "3") (pinfunction "C_3") (pintype "passive"))
    )
    (net (code "169") (name "/N4_5") (class "Default")
      (node (ref "N4") (pin "6") (pinfunction "5_6") (pintype "bidirectional"))
      (node (ref "T47") (pin "3") (pinfunction "C_3") (pintype "passive"))
    )
    (net (code "170") (name "/N4_6") (class "Default")
      (node (ref "N4") (pin "7") (pinfunction "6_7") (pintype "bidirectional"))
      (node (ref "T46") (pin "3") (pinfunction "C_3") (pintype "passive"))
    )
    (net (code "171") (name "/N4_7") (class "Default")
      (node (ref "N4") (pin "8") (pinfunction "7_8") (pintype "bidirectional"))
      (node (ref "T45") (pin "3") (pinfunction "C_3") (pintype "passive"))
    )
    (net (code "172") (name "/N4_8") (class "Default")
      (node (ref "N4") (pin "9") (pinfunction "8_9") (pintype "bidirectional"))
      (node (ref "T44") (pin "3") (pinfunction "C_3") (pintype "passive"))
    )
    (net (code "173") (name "/N4_9") (class "Default")
      (node (ref "N4") (pin "11") (pinfunction "9_11") (pintype "bidirectional"))
      (node (ref "T43") (pin "3") (pinfunction "C_3") (pintype "passive"))
    )
    (net (code "174") (name "/N5_0") (class "Default")
      (node (ref "N5") (pin "12") (pinfunction "0_12") (pintype "bidirectional"))
      (node (ref "T52") (pin "3") (pinfunction "C_3") (pintype "passive"))
    )
    (net (code "175") (name "/N5_1") (class "Default")
      (node (ref "N5") (pin "1") (pinfunction "1_1") (pintype "bidirectional"))
      (node (ref "T51") (pin "3") (pinfunction "C_3") (pintype "passive"))
    )
    (net (code "176") (name "/N5_2") (class "Default")
      (node (ref "N5") (pin "2") (pinfunction "2_2") (pintype "bidirectional"))
      (node (ref "T50") (pin "3") (pinfunction "C_3") (pintype "passive"))
    )
    (net (code "177") (name "/N5_3") (class "Default")
      (node (ref "N5") (pin "3") (pinfunction "3_3") (pintype "bidirectional"))
      (node (ref "T59") (pin "3") (pinfunction "C_3") (pintype "passive"))
    )
    (net (code "178") (name "/N5_4") (class "Default")
      (node (ref "N5") (pin "5") (pinfunction "4_5") (pintype "bidirectional"))
      (node (ref "T58") (pin "3") (pinfunction "C_3") (pintype "passive"))
    )
    (net (code "179") (name "/N5_5") (class "Default")
      (node (ref "N5") (pin "6") (pinfunction "5_6") (pintype "bidirectional"))
      (node (ref "T57") (pin "3") (pinfunction "C_3") (pintype "passive"))
    )
    (net (code "180") (name "/N5_6") (class "Default")
      (node (ref "N5") (pin "7") (pinfunction "6_7") (pintype "bidirectional"))
      (node (ref "T56") (pin "3") (pinfunction "C_3") (pintype "passive"))
    )
    (net (code "181") (name "/N5_7") (class "Default")
      (node (ref "N5") (pin "8") (pinfunction "7_8") (pintype "bidirectional"))
      (node (ref "T55") (pin "3") (pinfunction "C_3") (pintype "passive"))
    )
    (net (code "182") (name "/N5_8") (class "Default")
      (node (ref "N5") (pin "9") (pinfunction "8_9") (pintype "bidirectional"))
      (node (ref "T54") (pin "3") (pinfunction "C_3") (pintype "passive"))
    )
    (net (code "183") (name "/N5_9") (class "Default")
      (node (ref "N5") (pin "11") (pinfunction "9_11") (pintype "bidirectional"))
      (node (ref "T53") (pin "3") (pinfunction "C_3") (pintype "passive"))
    )
    (net (code "184") (name "/N6_0") (class "Default")
      (node (ref "N6") (pin "12") (pinfunction "0_12") (pintype "bidirectional"))
      (node (ref "T62") (pin "3") (pinfunction "C_3") (pintype "passive"))
    )
    (net (code "185") (name "/N6_1") (class "Default")
      (node (ref "N6") (pin "1") (pinfunction "1_1") (pintype "bidirectional"))
      (node (ref "T61") (pin "3") (pinfunction "C_3") (pintype "passive"))
    )
    (net (code "186") (name "/N6_2") (class "Default")
      (node (ref "N6") (pin "2") (pinfunction "2_2") (pintype "bidirectional"))
      (node (ref "T60") (pin "3") (pinfunction "C_3") (pintype "passive"))
    )
    (net (code "187") (name "/N6_3") (class "Default")
      (node (ref "N6") (pin "3") (pinfunction "3_3") (pintype "bidirectional"))
      (node (ref "T69") (pin "3") (pinfunction "C_3") (pintype "passive"))
    )
    (net (code "188") (name "/N6_4") (class "Default")
      (node (ref "N6") (pin "5") (pinfunction "4_5") (pintype "bidirectional"))
      (node (ref "T68") (pin "3") (pinfunction "C_3") (pintype "passive"))
    )
    (net (code "189") (name "/N6_5") (class "Default")
      (node (ref "N6") (pin "6") (pinfunction "5_6") (pintype "bidirectional"))
      (node (ref "T67") (pin "3") (pinfunction "C_3") (pintype "passive"))
    )
    (net (code "190") (name "/N6_6") (class "Default")
      (node (ref "N6") (pin "7") (pinfunction "6_7") (pintype "bidirectional"))
      (node (ref "T66") (pin "3") (pinfunction "C_3") (pintype "passive"))
    )
    (net (code "191") (name "/N6_7") (class "Default")
      (node (ref "N6") (pin "8") (pinfunction "7_8") (pintype "bidirectional"))
      (node (ref "T65") (pin "3") (pinfunction "C_3") (pintype "passive"))
    )
    (net (code "192") (name "/N6_8") (class "Default")
      (node (ref "N6") (pin "9") (pinfunction "8_9") (pintype "bidirectional"))
      (node (ref "T64") (pin "3") (pinfunction "C_3") (pintype "passive"))
    )
    (net (code "193") (name "/N6_9") (class "Default")
      (node (ref "N6") (pin "11") (pinfunction "9_11") (pintype "bidirectional"))
      (node (ref "T63") (pin "3") (pinfunction "C_3") (pintype "passive"))
    )
    (net (code "194") (name "/RCK") (class "Default")
      (node (ref "IC1") (pin "12") (pinfunction "RCK_12") (pintype "input"))
      (node (ref "IC2") (pin "12") (pinfunction "RCK_12") (pintype "input"))
      (node (ref "IC3") (pin "12") (pinfunction "RCK_12") (pintype "input"))
      (node (ref "IC4") (pin "12") (pinfunction "RCK_12") (pintype "input"))
      (node (ref "IC5") (pin "12") (pinfunction "RCK_12") (pintype "input"))
      (node (ref "IC6") (pin "12") (pinfunction "RCK_12") (pintype "input"))
      (node (ref "IC7") (pin "12") (pinfunction "RCK_12") (pintype "input"))
      (node (ref "IC8") (pin "12") (pinfunction "RCK_12") (pintype "input"))
      (node (ref "JP1") (pin "5") (pinfunction "5_5") (pintype "passive"))
    )
    (net (code "195") (name "/SCK") (class "Default")
      (node (ref "IC1") (pin "11") (pinfunction "SCK_11") (pintype "input"))
      (node (ref "IC2") (pin "11") (pinfunction "SCK_11") (pintype "input"))
      (node (ref "IC3") (pin "11") (pinfunction "SCK_11") (pintype "input"))
      (node (ref "IC4") (pin "11") (pinfunction "SCK_11") (pintype "input"))
      (node (ref "IC5") (pin "11") (pinfunction "SCK_11") (pintype "input"))
      (node (ref "IC6") (pin "11") (pinfunction "SCK_11") (pintype "input"))
      (node (ref "IC7") (pin "11") (pinfunction "SCK_11") (pintype "input"))
      (node (ref "IC8") (pin "11") (pinfunction "SCK_11") (pintype "input"))
      (node (ref "JP1") (pin "3") (pinfunction "3_3") (pintype "passive"))
    )
    (net (code "196") (name "/SCL") (class "Default")
      (node (ref "IC1") (pin "10") (pinfunction "SCL_10") (pintype "input"))
      (node (ref "IC2") (pin "10") (pinfunction "SCL_10") (pintype "input"))
      (node (ref "IC3") (pin "10") (pinfunction "SCL_10") (pintype "input"))
      (node (ref "IC4") (pin "10") (pinfunction "SCL_10") (pintype "input"))
      (node (ref "IC5") (pin "10") (pinfunction "SCL_10") (pintype "input"))
      (node (ref "IC6") (pin "10") (pinfunction "SCL_10") (pintype "input"))
      (node (ref "IC7") (pin "10") (pinfunction "SCL_10") (pintype "input"))
      (node (ref "IC8") (pin "10") (pinfunction "SCL_10") (pintype "input"))
      (node (ref "JP1") (pin "2") (pinfunction "2_2") (pintype "passive"))
    )
    (net (code "197") (name "GND") (class "Default")
      (node (ref "C1") (pin "2") (pinfunction "2_2") (pintype "passive"))
      (node (ref "C2") (pin "2") (pinfunction "2_2") (pintype "passive"))
      (node (ref "C3") (pin "2") (pinfunction "2_2") (pintype "passive"))
      (node (ref "C4") (pin "2") (pinfunction "2_2") (pintype "passive"))
      (node (ref "C5") (pin "2") (pinfunction "2_2") (pintype "passive"))
      (node (ref "C6") (pin "2") (pinfunction "2_2") (pintype "passive"))
      (node (ref "C7") (pin "2") (pinfunction "2_2") (pintype "passive"))
      (node (ref "C8") (pin "2") (pinfunction "2_2") (pintype "passive"))
      (node (ref "IC1") (pin "8") (pinfunction "GND_8") (pintype "power_in"))
      (node (ref "IC2") (pin "8") (pinfunction "GND_8") (pintype "power_in"))
      (node (ref "IC3") (pin "8") (pinfunction "GND_8") (pintype "power_in"))
      (node (ref "IC4") (pin "8") (pinfunction "GND_8") (pintype "power_in"))
      (node (ref "IC5") (pin "8") (pinfunction "GND_8") (pintype "power_in"))
      (node (ref "IC6") (pin "8") (pinfunction "GND_8") (pintype "power_in"))
      (node (ref "IC7") (pin "8") (pinfunction "GND_8") (pintype "power_in"))
      (node (ref "IC8") (pin "8") (pinfunction "GND_8") (pintype "power_in"))
      (node (ref "JP1") (pin "6") (pinfunction "6_6") (pintype "passive"))
      (node (ref "JP2") (pin "2") (pinfunction "2_2") (pintype "passive"))
      (node (ref "JP2") (pin "3") (pinfunction "3_3") (pintype "passive"))
      (node (ref "JP2") (pin "4") (pinfunction "4_4") (pintype "passive"))
      (node (ref "JP2") (pin "5") (pinfunction "5_5") (pintype "passive"))
      (node (ref "T1") (pin "2") (pinfunction "E_2") (pintype "passive"))
      (node (ref "T10") (pin "2") (pinfunction "E_2") (pintype "passive"))
      (node (ref "T11") (pin "2") (pinfunction "E_2") (pintype "passive"))
      (node (ref "T12") (pin "2") (pinfunction "E_2") (pintype "passive"))
      (node (ref "T13") (pin "2") (pinfunction "E_2") (pintype "passive"))
      (node (ref "T14") (pin "2") (pinfunction "E_2") (pintype "passive"))
      (node (ref "T15") (pin "2") (pinfunction "E_2") (pintype "passive"))
      (node (ref "T16") (pin "2") (pinfunction "E_2") (pintype "passive"))
      (node (ref "T17") (pin "2") (pinfunction "E_2") (pintype "passive"))
      (node (ref "T18") (pin "2") (pinfunction "E_2") (pintype "passive"))
      (node (ref "T19") (pin "2") (pinfunction "E_2") (pintype "passive"))
      (node (ref "T2") (pin "2") (pinfunction "E_2") (pintype "passive"))
      (node (ref "T20") (pin "2") (pinfunction "E_2") (pintype "passive"))
      (node (ref "T21") (pin "2") (pinfunction "E_2") (pintype "passive"))
      (node (ref "T22") (pin "2") (pinfunction "E_2") (pintype "passive"))
      (node (ref "T23") (pin "2") (pinfunction "E_2") (pintype "passive"))
      (node (ref "T24") (pin "2") (pinfunction "E_2") (pintype "passive"))
      (node (ref "T25") (pin "2") (pinfunction "E_2") (pintype "passive"))
      (node (ref "T26") (pin "2") (pinfunction "E_2") (pintype "passive"))
      (node (ref "T27") (pin "2") (pinfunction "E_2") (pintype "passive"))
      (node (ref "T28") (pin "2") (pinfunction "E_2") (pintype "passive"))
      (node (ref "T29") (pin "2") (pinfunction "E_2") (pintype "passive"))
      (node (ref "T3") (pin "2") (pinfunction "E_2") (pintype "passive"))
      (node (ref "T30") (pin "2") (pinfunction "E_2") (pintype "passive"))
      (node (ref "T31") (pin "2") (pinfunction "E_2") (pintype "passive"))
      (node (ref "T32") (pin "2") (pinfunction "E_2") (pintype "passive"))
      (node (ref "T33") (pin "2") (pinfunction "E_2") (pintype "passive"))
      (node (ref "T34") (pin "2") (pinfunction "E_2") (pintype "passive"))
      (node (ref "T35") (pin "2") (pinfunction "E_2") (pintype "passive"))
      (node (ref "T36") (pin "2") (pinfunction "E_2") (pintype "passive"))
      (node (ref "T37") (pin "2") (pinfunction "E_2") (pintype "passive"))
      (node (ref "T38") (pin "2") (pinfunction "E_2") (pintype "passive"))
      (node (ref "T39") (pin "2") (pinfunction "E_2") (pintype "passive"))
      (node (ref "T4") (pin "2") (pinfunction "E_2") (pintype "passive"))
      (node (ref "T40") (pin "2") (pinfunction "E_2") (pintype "passive"))
      (node (ref "T41") (pin "2") (pinfunction "E_2") (pintype "passive"))
      (node (ref "T42") (pin "2") (pinfunction "E_2") (pintype "passive"))
      (node (ref "T43") (pin "2") (pinfunction "E_2") (pintype "passive"))
      (node (ref "T44") (pin "2") (pinfunction "E_2") (pintype "passive"))
      (node (ref "T45") (pin "2") (pinfunction "E_2") (pintype "passive"))
      (node (ref "T46") (pin "2") (pinfunction "E_2") (pintype "passive"))
      (node (ref "T47") (pin "2") (pinfunction "E_2") (pintype "passive"))
      (node (ref "T48") (pin "2") (pinfunction "E_2") (pintype "passive"))
      (node (ref "T49") (pin "2") (pinfunction "E_2") (pintype "passive"))
      (node (ref "T50") (pin "2") (pinfunction "E_2") (pintype "passive"))
      (node (ref "T51") (pin "2") (pinfunction "E_2") (pintype "passive"))
      (node (ref "T52") (pin "2") (pinfunction "E_2") (pintype "passive"))
      (node (ref "T53") (pin "2") (pinfunction "E_2") (pintype "passive"))
      (node (ref "T54") (pin "2") (pinfunction "E_2") (pintype "passive"))
      (node (ref "T55") (pin "2") (pinfunction "E_2") (pintype "passive"))
      (node (ref "T56") (pin "2") (pinfunction "E_2") (pintype "passive"))
      (node (ref "T57") (pin "2") (pinfunction "E_2") (pintype "passive"))
      (node (ref "T58") (pin "2") (pinfunction "E_2") (pintype "passive"))
      (node (ref "T59") (pin "2") (pinfunction "E_2") (pintype "passive"))
      (node (ref "T60") (pin "2") (pinfunction "E_2") (pintype "passive"))
      (node (ref "T61") (pin "2") (pinfunction "E_2") (pintype "passive"))
      (node (ref "T62") (pin "2") (pinfunction "E_2") (pintype "passive"))
      (node (ref "T63") (pin "2") (pinfunction "E_2") (pintype "passive"))
      (node (ref "T64") (pin "2") (pinfunction "E_2") (pintype "passive"))
      (node (ref "T65") (pin "2") (pinfunction "E_2") (pintype "passive"))
      (node (ref "T66") (pin "2") (pinfunction "E_2") (pintype "passive"))
      (node (ref "T67") (pin "2") (pinfunction "E_2") (pintype "passive"))
      (node (ref "T68") (pin "2") (pinfunction "E_2") (pintype "passive"))
      (node (ref "T69") (pin "2") (pinfunction "E_2") (pintype "passive"))
    )
    (net (code "198") (name "Net-(GL1-A)") (class "Default")
      (node (ref "GL1") (pin "1") (pinfunction "A_1") (pintype "passive"))
      (node (ref "R1") (pin "1") (pinfunction "1_1") (pintype "passive"))
    )
    (net (code "199") (name "Net-(GL1-A1)") (class "Default")
      (node (ref "GL1") (pin "2") (pinfunction "A1_2") (pintype "passive"))
      (node (ref "T1") (pin "3") (pinfunction "C_3") (pintype "passive"))
    )
    (net (code "200") (name "Net-(GL2-A)") (class "Default")
      (node (ref "GL2") (pin "1") (pinfunction "A_1") (pintype "passive"))
      (node (ref "R2") (pin "1") (pinfunction "1_1") (pintype "passive"))
    )
    (net (code "201") (name "Net-(GL2-A1)") (class "Default")
      (node (ref "GL2") (pin "2") (pinfunction "A1_2") (pintype "passive"))
      (node (ref "T2") (pin "3") (pinfunction "C_3") (pintype "passive"))
    )
    (net (code "202") (name "Net-(GL3-A)") (class "Default")
      (node (ref "GL3") (pin "1") (pinfunction "A_1") (pintype "passive"))
      (node (ref "R3") (pin "1") (pinfunction "1_1") (pintype "passive"))
    )
    (net (code "203") (name "Net-(GL3-A1)") (class "Default")
      (node (ref "GL3") (pin "2") (pinfunction "A1_2") (pintype "passive"))
      (node (ref "T3") (pin "3") (pinfunction "C_3") (pintype "passive"))
    )
    (net (code "204") (name "Net-(GL4-A)") (class "Default")
      (node (ref "GL4") (pin "1") (pinfunction "A_1") (pintype "passive"))
      (node (ref "R4") (pin "1") (pinfunction "1_1") (pintype "passive"))
    )
    (net (code "205") (name "Net-(GL4-A1)") (class "Default")
      (node (ref "GL4") (pin "2") (pinfunction "A1_2") (pintype "passive"))
      (node (ref "T4") (pin "3") (pinfunction "C_3") (pintype "passive"))
    )
    (net (code "206") (name "Net-(IC1A-QH*)") (class "Default")
      (node (ref "IC1") (pin "9") (pinfunction "QH*_9") (pintype "tri_state"))
      (node (ref "IC2") (pin "14") (pinfunction "SER_14") (pintype "input"))
    )
    (net (code "207") (name "Net-(IC2A-QH*)") (class "Default")
      (node (ref "IC2") (pin "9") (pinfunction "QH*_9") (pintype "tri_state"))
      (node (ref "IC3") (pin "14") (pinfunction "SER_14") (pintype "input"))
    )
    (net (code "208") (name "Net-(IC3A-QH*)") (class "Default")
      (node (ref "IC3") (pin "9") (pinfunction "QH*_9") (pintype "tri_state"))
      (node (ref "IC4") (pin "14") (pinfunction "SER_14") (pintype "input"))
    )
    (net (code "209") (name "Net-(IC4A-QH*)") (class "Default")
      (node (ref "IC4") (pin "9") (pinfunction "QH*_9") (pintype "tri_state"))
      (node (ref "IC5") (pin "14") (pinfunction "SER_14") (pintype "input"))
    )
    (net (code "210") (name "Net-(IC5A-QH*)") (class "Default")
      (node (ref "IC5") (pin "9") (pinfunction "QH*_9") (pintype "tri_state"))
      (node (ref "IC6") (pin "14") (pinfunction "SER_14") (pintype "input"))
    )
    (net (code "211") (name "Net-(IC6A-QH*)") (class "Default")
      (node (ref "IC6") (pin "9") (pinfunction "QH*_9") (pintype "tri_state"))
      (node (ref "IC7") (pin "14") (pinfunction "SER_14") (pintype "input"))
    )
    (net (code "212") (name "Net-(IC7A-QH*)") (class "Default")
      (node (ref "IC7") (pin "9") (pinfunction "QH*_9") (pintype "tri_state"))
      (node (ref "IC8") (pin "14") (pinfunction "SER_14") (pintype "input"))
    )
    (net (code "213") (name "Net-(N1-A)") (class "Default")
      (node (ref "N1") (pin "13") (pinfunction "A_13") (pintype "bidirectional"))
      (node (ref "R20") (pin "1") (pinfunction "1_1") (pintype "passive"))
    )
    (net (code "214") (name "Net-(N2-A)") (class "Default")
      (node (ref "N2") (pin "13") (pinfunction "A_13") (pintype "bidirectional"))
      (node (ref "R10") (pin "1") (pinfunction "1_1") (pintype "passive"))
    )
    (net (code "215") (name "Net-(N3-A)") (class "Default")
      (node (ref "N3") (pin "13") (pinfunction "A_13") (pintype "bidirectional"))
      (node (ref "R30") (pin "1") (pinfunction "1_1") (pintype "passive"))
    )
    (net (code "216") (name "Net-(N4-A)") (class "Default")
      (node (ref "N4") (pin "13") (pinfunction "A_13") (pintype "bidirectional"))
      (node (ref "R40") (pin "1") (pinfunction "1_1") (pintype "passive"))
    )
    (net (code "217") (name "Net-(N5-A)") (class "Default")
      (node (ref "N5") (pin "13") (pinfunction "A_13") (pintype "bidirectional"))
      (node (ref "R50") (pin "1") (pinfunction "1_1") (pintype "passive"))
    )
    (net (code "218") (name "Net-(N6-A)") (class "Default")
      (node (ref "N6") (pin "13") (pinfunction "A_13") (pintype "bidirectional"))
      (node (ref "R60") (pin "1") (pinfunction "1_1") (pintype "passive"))
    )
    (net (code "219") (name "VDD") (class "Default")
      (node (ref "JP2") (pin "1") (pinfunction "1_1") (pintype "passive"))
      (node (ref "R1") (pin "2") (pinfunction "2_2") (pintype "passive"))
      (node (ref "R10") (pin "2") (pinfunction "2_2") (pintype "passive"))
      (node (ref "R2") (pin "2") (pinfunction "2_2") (pintype "passive"))
      (node (ref "R20") (pin "2") (pinfunction "2_2") (pintype "passive"))
      (node (ref "R3") (pin "2") (pinfunction "2_2") (pintype "passive"))
      (node (ref "R30") (pin "2") (pinfunction "2_2") (pintype "passive"))
      (node (ref "R4") (pin "2") (pinfunction "2_2") (pintype "passive"))
      (node (ref "R40") (pin "2") (pinfunction "2_2") (pintype "passive"))
      (node (ref "R50") (pin "2") (pinfunction "2_2") (pintype "passive"))
      (node (ref "R60") (pin "2") (pinfunction "2_2") (pintype "passive"))
    )
    (net (code "220") (name "unconnected-(IC8A-QH*-Pad9)") (class "Default")
      (node (ref "IC8") (pin "9") (pinfunction "QH*_9") (pintype "tri_state"))
    )
    (net (code "221") (name "unconnected-(N1-DP-Pad10)") (class "Default")
      (node (ref "N1") (pin "10") (pinfunction "DP_10") (pintype "bidirectional"))
    )
    (net (code "222") (name "unconnected-(N1-IC-Pad4)") (class "Default")
      (node (ref "N1") (pin "4") (pinfunction "IC_4") (pintype "bidirectional"))
    )
    (net (code "223") (name "unconnected-(N3-DP-Pad10)") (class "Default")
      (node (ref "N3") (pin "10") (pinfunction "DP_10") (pintype "bidirectional"))
    )
    (net (code "224") (name "unconnected-(N3-IC-Pad4)") (class "Default")
      (node (ref "N3") (pin "4") (pinfunction "IC_4") (pintype "bidirectional"))
    )
    (net (code "225") (name "unconnected-(N4-DP-Pad10)") (class "Default")
      (node (ref "N4") (pin "10") (pinfunction "DP_10") (pintype "bidirectional"))
    )
    (net (code "226") (name "unconnected-(N4-IC-Pad4)") (class "Default")
      (node (ref "N4") (pin "4") (pinfunction "IC_4") (pintype "bidirectional"))
    )
    (net (code "227") (name "unconnected-(N5-DP-Pad10)") (class "Default")
      (node (ref "N5") (pin "10") (pinfunction "DP_10") (pintype "bidirectional"))
    )
    (net (code "228") (name "unconnected-(N5-IC-Pad4)") (class "Default")
      (node (ref "N5") (pin "4") (pinfunction "IC_4") (pintype "bidirectional"))
    )
    (net (code "229") (name "unconnected-(N6-DP-Pad10)") (class "Default")
      (node (ref "N6") (pin "10") (pinfunction "DP_10") (pintype "bidirectional"))
    )
    (net (code "230") (name "unconnected-(N6-IC-Pad4)") (class "Default")
      (node (ref "N6") (pin "4") (pinfunction "IC_4") (pintype "bidirectional"))
    )
  )
)
